# CC2530_PCB_Updated_Antenna_Stim_EMG-ROAC.net
KiCad netlist of a schematic drawn in EAGLE
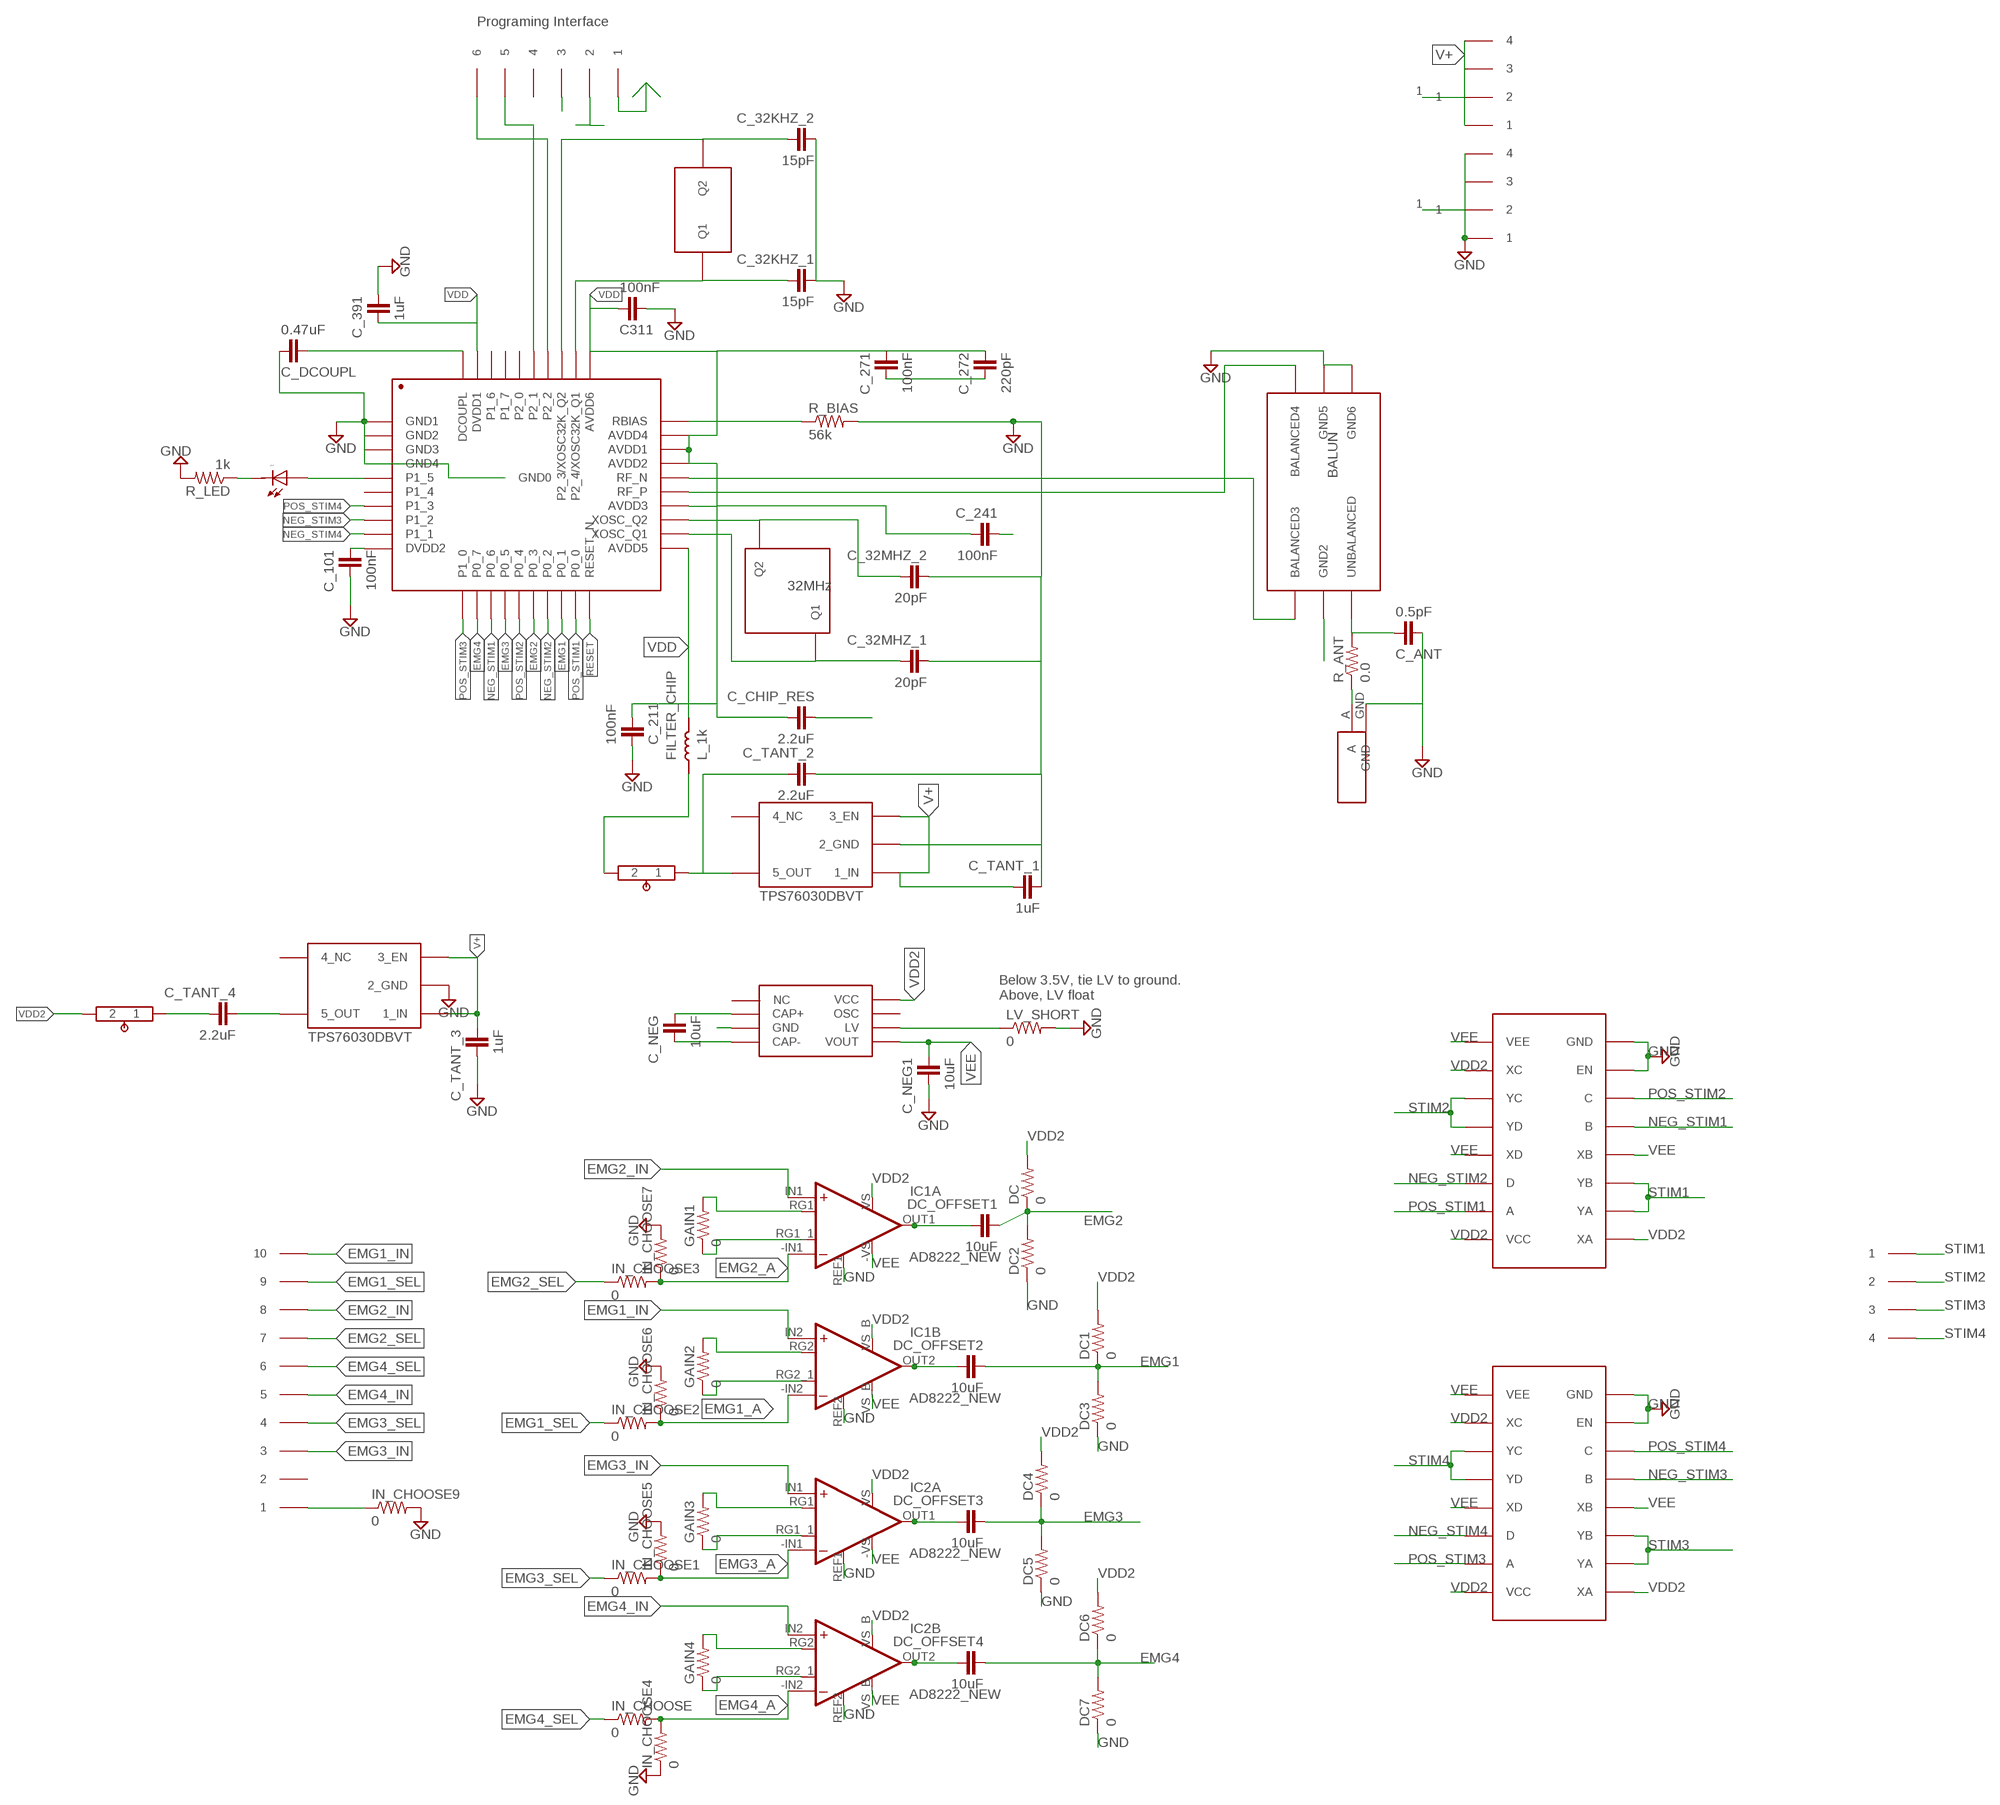
[diagram p0: schematic, sheet 1]

(export (version "E")
  (design (tool "Eeschema 10.0.6"))
  (components
    (comp (ref "32KHZ")
      (value "X32.768KHZ")
      (footprint "eagle-import:X32.768KHZ")
      (libsource (lib "eagle-import") (part "X32.768KHZ"))
    )
    (comp (ref "C311")
      (value "100nF")
      (footprint "eagle-import:0201_R_L_C")
      (libsource (lib "eagle-import") (part "0Y0X_C0201"))
    )
    (comp (ref "C_32KHZ_1")
      (value "15pF")
      (footprint "eagle-import:0201_R_L_C")
      (libsource (lib "eagle-import") (part "0Y0X_C0201"))
    )
    (comp (ref "C_32KHZ_2")
      (value "15pF")
      (footprint "eagle-import:0201_R_L_C")
      (libsource (lib "eagle-import") (part "0Y0X_C0201"))
    )
    (comp (ref "C_32MHZ_1")
      (value "20pF")
      (footprint "eagle-import:0201_R_L_C")
      (libsource (lib "eagle-import") (part "0Y0X_C0201"))
    )
    (comp (ref "C_32MHZ_2")
      (value "20pF")
      (footprint "eagle-import:0201_R_L_C")
      (libsource (lib "eagle-import") (part "0Y0X_C0201"))
    )
    (comp (ref "C_101")
      (value "100nF")
      (footprint "eagle-import:0201_R_L_C")
      (libsource (lib "eagle-import") (part "0Y0X_C0201"))
    )
    (comp (ref "C_211")
      (value "100nF")
      (footprint "eagle-import:0201_R_L_C")
      (libsource (lib "eagle-import") (part "0Y0X_C0201"))
    )
    (comp (ref "C_241")
      (value "100nF")
      (footprint "eagle-import:0201_R_L_C")
      (libsource (lib "eagle-import") (part "0Y0X_C0201"))
    )
    (comp (ref "C_271")
      (value "100nF")
      (footprint "eagle-import:0201_R_L_C")
      (libsource (lib "eagle-import") (part "0Y0X_C0201"))
    )
    (comp (ref "C_272")
      (value "220pF")
      (footprint "eagle-import:0201_R_L_C")
      (libsource (lib "eagle-import") (part "0Y0X_C0201"))
    )
    (comp (ref "C_391")
      (value "1uF")
      (footprint "eagle-import:0201_R_L_C")
      (libsource (lib "eagle-import") (part "0Y0X_C0201"))
    )
    (comp (ref "C_ANT")
      (value "0.5pF")
      (footprint "eagle-import:0201_R_L_C")
      (libsource (lib "eagle-import") (part "0Y0X_C0201"))
    )
    (comp (ref "C_CHIP_RES")
      (value "2.2uF")
      (footprint "eagle-import:0402_R_L_C")
      (libsource (lib "eagle-import") (part "0Y0X_C0402"))
    )
    (comp (ref "C_DCOUPL")
      (value "0.47uF")
      (footprint "eagle-import:0201_R_L_C")
      (libsource (lib "eagle-import") (part "0Y0X_C0201"))
    )
    (comp (ref "C_NEG")
      (value "10uF")
      (footprint "eagle-import:0402_R_L_C")
      (libsource (lib "eagle-import") (part "0Y0X_C0402"))
    )
    (comp (ref "C_NEG1")
      (value "10uF")
      (footprint "eagle-import:0402_R_L_C")
      (libsource (lib "eagle-import") (part "0Y0X_C0402"))
    )
    (comp (ref "C_TANT_1")
      (value "1uF")
      (footprint "eagle-import:0603_R_L_C")
      (libsource (lib "eagle-import") (part "0Y0X_C0603"))
    )
    (comp (ref "C_TANT_2")
      (value "2.2uF")
      (footprint "eagle-import:0603_R_L_C")
      (libsource (lib "eagle-import") (part "0Y0X_C0603"))
    )
    (comp (ref "C_TANT_3")
      (value "1uF")
      (footprint "eagle-import:0603_R_L_C")
      (libsource (lib "eagle-import") (part "0Y0X_C0603"))
    )
    (comp (ref "C_TANT_4")
      (value "2.2uF")
      (footprint "eagle-import:0603_R_L_C")
      (libsource (lib "eagle-import") (part "0Y0X_C0603"))
    )
    (comp (ref "DC")
      (value "0")
      (footprint "eagle-import:0402_R_L_C")
      (libsource (lib "eagle-import") (part "0Y0X_R0402"))
    )
    (comp (ref "DC1")
      (value "0")
      (footprint "eagle-import:0402_R_L_C")
      (libsource (lib "eagle-import") (part "0Y0X_R0402"))
    )
    (comp (ref "DC2")
      (value "0")
      (footprint "eagle-import:0402_R_L_C")
      (libsource (lib "eagle-import") (part "0Y0X_R0402"))
    )
    (comp (ref "DC3")
      (value "0")
      (footprint "eagle-import:0402_R_L_C")
      (libsource (lib "eagle-import") (part "0Y0X_R0402"))
    )
    (comp (ref "DC4")
      (value "0")
      (footprint "eagle-import:0402_R_L_C")
      (libsource (lib "eagle-import") (part "0Y0X_R0402"))
    )
    (comp (ref "DC5")
      (value "0")
      (footprint "eagle-import:0402_R_L_C")
      (libsource (lib "eagle-import") (part "0Y0X_R0402"))
    )
    (comp (ref "DC6")
      (value "0")
      (footprint "eagle-import:0402_R_L_C")
      (libsource (lib "eagle-import") (part "0Y0X_R0402"))
    )
    (comp (ref "DC7")
      (value "0")
      (footprint "eagle-import:0402_R_L_C")
      (libsource (lib "eagle-import") (part "0Y0X_R0402"))
    )
    (comp (ref "DC_OFFSET1")
      (value "10uF")
      (footprint "eagle-import:0402_R_L_C")
      (libsource (lib "eagle-import") (part "0Y0X_C0402"))
    )
    (comp (ref "DC_OFFSET2")
      (value "10uF")
      (footprint "eagle-import:0402_R_L_C")
      (libsource (lib "eagle-import") (part "0Y0X_C0402"))
    )
    (comp (ref "DC_OFFSET3")
      (value "10uF")
      (footprint "eagle-import:0402_R_L_C")
      (libsource (lib "eagle-import") (part "0Y0X_C0402"))
    )
    (comp (ref "DC_OFFSET4")
      (value "10uF")
      (footprint "eagle-import:0402_R_L_C")
      (libsource (lib "eagle-import") (part "0Y0X_C0402"))
    )
    (comp (ref "FILTER_CHIP")
      (value "L_1k")
      (footprint "eagle-import:0402_R_L_C")
      (libsource (lib "eagle-import") (part "0Y0X_L0402"))
    )
    (comp (ref "GAIN1")
      (value "0")
      (footprint "eagle-import:0402_R_L_C")
      (libsource (lib "eagle-import") (part "0Y0X_R0402"))
    )
    (comp (ref "GAIN2")
      (value "0")
      (footprint "eagle-import:0402_R_L_C")
      (libsource (lib "eagle-import") (part "0Y0X_R0402"))
    )
    (comp (ref "GAIN3")
      (value "0")
      (footprint "eagle-import:0402_R_L_C")
      (libsource (lib "eagle-import") (part "0Y0X_R0402"))
    )
    (comp (ref "GAIN4")
      (value "0")
      (footprint "eagle-import:0402_R_L_C")
      (libsource (lib "eagle-import") (part "0Y0X_R0402"))
    )
    (comp (ref "GND_IN")
      (value "FFC4POS")
      (footprint "eagle-import:FFC4POS")
      (libsource (lib "eagle-import") (part "FFC4POS"))
    )
    (comp (ref "IC1")
      (value "AD8222_NEW")
      (footprint "eagle-import:QFN-16")
      (libsource (lib "eagle-import") (part "AD8222_NEW"))
    )
    (comp (ref "IC2")
      (value "AD8222_NEW")
      (footprint "eagle-import:QFN-16")
      (libsource (lib "eagle-import") (part "AD8222_NEW"))
    )
    (comp (ref "INVERTED_F-ANTENNA")
      (value "ANTENNA")
      (footprint "eagle-import:ANTENNA")
      (libsource (lib "eagle-import") (part "ANTENNA"))
    )
    (comp (ref "IN_CHOOSE")
      (value "0")
      (footprint "eagle-import:0201_R_L_C")
      (libsource (lib "eagle-import") (part "0Y0X_R0201"))
    )
    (comp (ref "IN_CHOOSE1")
      (value "0")
      (footprint "eagle-import:0201_R_L_C")
      (libsource (lib "eagle-import") (part "0Y0X_R0201"))
    )
    (comp (ref "IN_CHOOSE2")
      (value "0")
      (footprint "eagle-import:0201_R_L_C")
      (libsource (lib "eagle-import") (part "0Y0X_R0201"))
    )
    (comp (ref "IN_CHOOSE3")
      (value "0")
      (footprint "eagle-import:0201_R_L_C")
      (libsource (lib "eagle-import") (part "0Y0X_R0201"))
    )
    (comp (ref "IN_CHOOSE4")
      (value "0")
      (footprint "eagle-import:0201_R_L_C")
      (libsource (lib "eagle-import") (part "0Y0X_R0201"))
    )
    (comp (ref "IN_CHOOSE5")
      (value "0")
      (footprint "eagle-import:0201_R_L_C")
      (libsource (lib "eagle-import") (part "0Y0X_R0201"))
    )
    (comp (ref "IN_CHOOSE6")
      (value "0")
      (footprint "eagle-import:0201_R_L_C")
      (libsource (lib "eagle-import") (part "0Y0X_R0201"))
    )
    (comp (ref "IN_CHOOSE7")
      (value "0")
      (footprint "eagle-import:0201_R_L_C")
      (libsource (lib "eagle-import") (part "0Y0X_R0201"))
    )
    (comp (ref "IN_CHOOSE9")
      (value "0")
      (footprint "eagle-import:0201_R_L_C")
      (libsource (lib "eagle-import") (part "0Y0X_R0201"))
    )
    (comp (ref "LED")
      (value "LED0603")
      (footprint "eagle-import:0603_R_L_C")
      (libsource (lib "eagle-import") (part "LED0603"))
    )
    (comp (ref "LV_SHORT")
      (value "0")
      (footprint "eagle-import:0402_R_L_C")
      (libsource (lib "eagle-import") (part "0Y0X_R0402"))
    )
    (comp (ref "R_ANT")
      (value "0.0")
      (footprint "eagle-import:0201_R_L_C")
      (libsource (lib "eagle-import") (part "0Y0X_R0201"))
    )
    (comp (ref "R_BIAS")
      (value "56k")
      (footprint "eagle-import:0201_R_L_C")
      (libsource (lib "eagle-import") (part "0Y0X_R0201"))
    )
    (comp (ref "R_LED")
      (value "1k")
      (footprint "eagle-import:0402_R_L_C")
      (libsource (lib "eagle-import") (part "0Y0X_R0402"))
    )
    (comp (ref "U$1")
      (value "CC2530")
      (footprint "eagle-import:CC2530")
      (libsource (lib "eagle-import") (part "CC2530"))
    )
    (comp (ref "U$2")
      (value "BALUN")
      (footprint "eagle-import:BALUN")
      (libsource (lib "eagle-import") (part "BALUN"))
    )
    (comp (ref "U$3")
      (value "X32MHZ")
      (footprint "eagle-import:X32MHZ")
      (fields (field (name "X") "32MHz"))
      (libsource (lib "eagle-import") (part "X32MHZ"))
    )
    (comp (ref "U$4")
      (value "TL7660")
      (footprint "eagle-import:S-PDSO-G8")
      (libsource (lib "eagle-import") (part "TL7660"))
    )
    (comp (ref "U$5")
      (value "MC74HC4316A")
      (footprint "eagle-import:SOIC-16-ON-SEMI")
      (libsource (lib "eagle-import") (part "MC74HC4316A"))
    )
    (comp (ref "U$6")
      (value "MC74HC4316A")
      (footprint "eagle-import:SOIC-16-ON-SEMI")
      (libsource (lib "eagle-import") (part "MC74HC4316A"))
    )
    (comp (ref "U$7")
      (value "FFC10POS")
      (footprint "eagle-import:FFC10POS")
      (libsource (lib "eagle-import") (part "FFC10POS"))
    )
    (comp (ref "U$8")
      (value "REGULATOR")
      (footprint "eagle-import:REGULATOR")
      (libsource (lib "eagle-import") (part "REGULATOR"))
    )
    (comp (ref "U$9")
      (value "SWITCH_MANUAL")
      (footprint "eagle-import:SWITCH_MANUAL")
      (libsource (lib "eagle-import") (part "SWITCH_MANUAL"))
    )
    (comp (ref "U$10")
      (value "REGULATOR")
      (footprint "eagle-import:REGULATOR")
      (libsource (lib "eagle-import") (part "REGULATOR"))
    )
    (comp (ref "U$17")
      (value "FFC6POS")
      (footprint "eagle-import:FFC6POS")
      (libsource (lib "eagle-import") (part "FFC6POS"))
    )
    (comp (ref "U$18")
      (value "SWITCH_MANUAL")
      (footprint "eagle-import:SWITCH_MANUAL")
      (libsource (lib "eagle-import") (part "SWITCH_MANUAL"))
    )
    (comp (ref "U$28")
      (value "FFC4POS")
      (footprint "eagle-import:FFC4POS")
      (libsource (lib "eagle-import") (part "FFC4POS"))
    )
    (comp (ref "V+_IN")
      (value "FFC4POS")
      (footprint "eagle-import:FFC4POS")
      (libsource (lib "eagle-import") (part "FFC4POS"))
    )
    (comp (ref "WIRE+")
      (value "DRILL_CONNECT")
      (footprint "eagle-import:DRILL_CONNECT")
      (libsource (lib "eagle-import") (part "DRILL_CONNECT"))
    )
    (comp (ref "WIRE-")
      (value "DRILL_CONNECT")
      (footprint "eagle-import:DRILL_CONNECT")
      (libsource (lib "eagle-import") (part "DRILL_CONNECT"))
    )
  )
  (nets
    (net (code "1") (name "/NC") (class "Default")
      (node (ref "U$4") (pin "1") (pinfunction "NC_1") (pintype "power_in"))
    )
    (net (code "2") (name "/OSC") (class "Default")
      (node (ref "U$4") (pin "7") (pinfunction "OSC_7") (pintype "power_in"))
    )
    (net (code "3") (name "/STIM1") (class "Default")
      (node (ref "U$28") (pin "1") (pinfunction "1_1") (pintype "bidirectional"))
      (node (ref "U$5") (pin "2") (pinfunction "YA_2") (pintype "output"))
      (node (ref "U$5") (pin "3") (pinfunction "YB_3") (pintype "output"))
    )
    (net (code "4") (name "/STIM2") (class "Default")
      (node (ref "U$28") (pin "2") (pinfunction "2_2") (pintype "bidirectional"))
      (node (ref "U$5") (pin "11") (pinfunction "YC_11") (pintype "output"))
      (node (ref "U$5") (pin "12") (pinfunction "YD_12") (pintype "output"))
    )
    (net (code "5") (name "/STIM3") (class "Default")
      (node (ref "U$28") (pin "3") (pinfunction "3_3") (pintype "bidirectional"))
      (node (ref "U$6") (pin "2") (pinfunction "YA_2") (pintype "output"))
      (node (ref "U$6") (pin "3") (pinfunction "YB_3") (pintype "output"))
    )
    (net (code "6") (name "/STIM4") (class "Default")
      (node (ref "U$28") (pin "4") (pinfunction "4_4") (pintype "bidirectional"))
      (node (ref "U$6") (pin "11") (pinfunction "YC_11") (pintype "output"))
      (node (ref "U$6") (pin "12") (pinfunction "YD_12") (pintype "output"))
    )
    (net (code "7") (name "EMG1") (class "Default")
      (node (ref "DC1") (pin "1") (pinfunction "1_1") (pintype "passive"))
      (node (ref "DC3") (pin "2") (pinfunction "2_2") (pintype "passive"))
      (node (ref "DC_OFFSET2") (pin "2") (pinfunction "2_2") (pintype "passive"))
      (node (ref "U$1") (pin "P0_1") (pinfunction "P0_1_P0_1") (pintype "bidirectional"))
    )
    (net (code "8") (name "EMG1_A") (class "Default")
      (node (ref "IC1") (pin "-IN2") (pinfunction "-IN_-IN2") (pintype "input"))
      (node (ref "IN_CHOOSE2") (pin "2") (pinfunction "2_2") (pintype "passive"))
      (node (ref "IN_CHOOSE6") (pin "1") (pinfunction "1_1") (pintype "passive"))
    )
    (net (code "9") (name "EMG1_IN") (class "Default")
      (node (ref "IC1") (pin "IN2") (pinfunction "+IN_IN2") (pintype "input"))
      (node (ref "U$7") (pin "10") (pinfunction "10_10") (pintype "bidirectional"))
    )
    (net (code "10") (name "EMG1_SEL") (class "Default")
      (node (ref "IN_CHOOSE2") (pin "1") (pinfunction "1_1") (pintype "passive"))
      (node (ref "U$7") (pin "9") (pinfunction "9_9") (pintype "bidirectional"))
    )
    (net (code "11") (name "EMG2") (class "Default")
      (node (ref "DC") (pin "1") (pinfunction "1_1") (pintype "passive"))
      (node (ref "DC2") (pin "2") (pinfunction "2_2") (pintype "passive"))
      (node (ref "DC_OFFSET1") (pin "2") (pinfunction "2_2") (pintype "passive"))
      (node (ref "U$1") (pin "P0_3") (pinfunction "P0_3_P0_3") (pintype "bidirectional"))
    )
    (net (code "12") (name "EMG2_A") (class "Default")
      (node (ref "IC1") (pin "-IN1") (pinfunction "-IN_-IN1") (pintype "input"))
      (node (ref "IN_CHOOSE3") (pin "2") (pinfunction "2_2") (pintype "passive"))
      (node (ref "IN_CHOOSE7") (pin "1") (pinfunction "1_1") (pintype "passive"))
    )
    (net (code "13") (name "EMG2_IN") (class "Default")
      (node (ref "IC1") (pin "IN1") (pinfunction "+IN_IN1") (pintype "input"))
      (node (ref "U$7") (pin "8") (pinfunction "8_8") (pintype "bidirectional"))
    )
    (net (code "14") (name "EMG2_SEL") (class "Default")
      (node (ref "IN_CHOOSE3") (pin "1") (pinfunction "1_1") (pintype "passive"))
      (node (ref "U$7") (pin "7") (pinfunction "7_7") (pintype "bidirectional"))
    )
    (net (code "15") (name "EMG3") (class "Default")
      (node (ref "DC4") (pin "1") (pinfunction "1_1") (pintype "passive"))
      (node (ref "DC5") (pin "2") (pinfunction "2_2") (pintype "passive"))
      (node (ref "DC_OFFSET3") (pin "2") (pinfunction "2_2") (pintype "passive"))
      (node (ref "U$1") (pin "P0_5") (pinfunction "P0_5_P0_5") (pintype "bidirectional"))
    )
    (net (code "16") (name "EMG3_A") (class "Default")
      (node (ref "IC2") (pin "-IN1") (pinfunction "-IN_-IN1") (pintype "input"))
      (node (ref "IN_CHOOSE1") (pin "2") (pinfunction "2_2") (pintype "passive"))
      (node (ref "IN_CHOOSE5") (pin "1") (pinfunction "1_1") (pintype "passive"))
    )
    (net (code "17") (name "EMG3_IN") (class "Default")
      (node (ref "IC2") (pin "IN1") (pinfunction "+IN_IN1") (pintype "input"))
      (node (ref "U$7") (pin "3") (pinfunction "3_3") (pintype "bidirectional"))
    )
    (net (code "18") (name "EMG3_SEL") (class "Default")
      (node (ref "IN_CHOOSE1") (pin "1") (pinfunction "1_1") (pintype "passive"))
      (node (ref "U$7") (pin "4") (pinfunction "4_4") (pintype "bidirectional"))
    )
    (net (code "19") (name "EMG4") (class "Default")
      (node (ref "DC6") (pin "1") (pinfunction "1_1") (pintype "passive"))
      (node (ref "DC7") (pin "2") (pinfunction "2_2") (pintype "passive"))
      (node (ref "DC_OFFSET4") (pin "2") (pinfunction "2_2") (pintype "passive"))
      (node (ref "U$1") (pin "P0_7") (pinfunction "P0_7_P0_7") (pintype "bidirectional"))
    )
    (net (code "20") (name "EMG4_A") (class "Default")
      (node (ref "IC2") (pin "-IN2") (pinfunction "-IN_-IN2") (pintype "input"))
      (node (ref "IN_CHOOSE") (pin "2") (pinfunction "2_2") (pintype "passive"))
      (node (ref "IN_CHOOSE4") (pin "2") (pinfunction "2_2") (pintype "passive"))
    )
    (net (code "21") (name "EMG4_IN") (class "Default")
      (node (ref "IC2") (pin "IN2") (pinfunction "+IN_IN2") (pintype "input"))
      (node (ref "U$7") (pin "5") (pinfunction "5_5") (pintype "bidirectional"))
    )
    (net (code "22") (name "EMG4_SEL") (class "Default")
      (node (ref "IN_CHOOSE") (pin "1") (pinfunction "1_1") (pintype "passive"))
      (node (ref "U$7") (pin "6") (pinfunction "6_6") (pintype "bidirectional"))
    )
    (net (code "23") (name "GND") (class "Default")
      (node (ref "C311") (pin "1") (pinfunction "1_1") (pintype "passive"))
      (node (ref "C_101") (pin "1") (pinfunction "1_1") (pintype "passive"))
      (node (ref "C_211") (pin "2") (pinfunction "2_2") (pintype "passive"))
      (node (ref "C_241") (pin "2") (pinfunction "2_2") (pintype "passive"))
      (node (ref "C_271") (pin "1") (pinfunction "1_1") (pintype "passive"))
      (node (ref "C_272") (pin "1") (pinfunction "1_1") (pintype "passive"))
      (node (ref "C_32KHZ_1") (pin "2") (pinfunction "2_2") (pintype "passive"))
      (node (ref "C_32KHZ_2") (pin "2") (pinfunction "2_2") (pintype "passive"))
      (node (ref "C_32MHZ_1") (pin "2") (pinfunction "2_2") (pintype "passive"))
      (node (ref "C_32MHZ_2") (pin "2") (pinfunction "2_2") (pintype "passive"))
      (node (ref "C_391") (pin "2") (pinfunction "2_2") (pintype "passive"))
      (node (ref "C_ANT") (pin "1") (pinfunction "1_1") (pintype "passive"))
      (node (ref "C_CHIP_RES") (pin "2") (pinfunction "2_2") (pintype "passive"))
      (node (ref "C_DCOUPL") (pin "2") (pinfunction "2_2") (pintype "passive"))
      (node (ref "C_NEG1") (pin "1") (pinfunction "1_1") (pintype "passive"))
      (node (ref "C_TANT_1") (pin "2") (pinfunction "2_2") (pintype "passive"))
      (node (ref "C_TANT_2") (pin "2") (pinfunction "2_2") (pintype "passive"))
      (node (ref "C_TANT_3") (pin "1") (pinfunction "1_1") (pintype "passive"))
      (node (ref "DC2") (pin "1") (pinfunction "1_1") (pintype "passive"))
      (node (ref "DC3") (pin "1") (pinfunction "1_1") (pintype "passive"))
      (node (ref "DC5") (pin "1") (pinfunction "1_1") (pintype "passive"))
      (node (ref "DC7") (pin "1") (pinfunction "1_1") (pintype "passive"))
      (node (ref "GND_IN") (pin "1") (pinfunction "1_1") (pintype "bidirectional"))
      (node (ref "GND_IN") (pin "2") (pinfunction "2_2") (pintype "bidirectional"))
      (node (ref "GND_IN") (pin "3") (pinfunction "3_3") (pintype "bidirectional"))
      (node (ref "GND_IN") (pin "4") (pinfunction "4_4") (pintype "bidirectional"))
      (node (ref "IC1") (pin "REF1") (pinfunction "REF_REF1") (pintype "input"))
      (node (ref "IC1") (pin "REF2") (pinfunction "REF_REF2") (pintype "input"))
      (node (ref "IC2") (pin "REF1") (pinfunction "REF_REF1") (pintype "input"))
      (node (ref "IC2") (pin "REF2") (pinfunction "REF_REF2") (pintype "input"))
      (node (ref "INVERTED_F-ANTENNA") (pin "GND") (pinfunction "GND_GND") (pintype "power_in"))
      (node (ref "IN_CHOOSE4") (pin "1") (pinfunction "1_1") (pintype "passive"))
      (node (ref "IN_CHOOSE5") (pin "2") (pinfunction "2_2") (pintype "passive"))
      (node (ref "IN_CHOOSE6") (pin "2") (pinfunction "2_2") (pintype "passive"))
      (node (ref "IN_CHOOSE7") (pin "2") (pinfunction "2_2") (pintype "passive"))
      (node (ref "IN_CHOOSE9") (pin "2") (pinfunction "2_2") (pintype "passive"))
      (node (ref "LV_SHORT") (pin "2") (pinfunction "2_2") (pintype "passive"))
      (node (ref "R_BIAS") (pin "2") (pinfunction "2_2") (pintype "passive"))
      (node (ref "R_LED") (pin "2") (pinfunction "2_2") (pintype "passive"))
      (node (ref "U$1") (pin "GND0") (pinfunction "GND0_GND0") (pintype "power_in"))
      (node (ref "U$1") (pin "GND001") (pinfunction "GND0_GND001") (pintype "power_in"))
      (node (ref "U$1") (pin "GND002") (pinfunction "GND0_GND002") (pintype "power_in"))
      (node (ref "U$1") (pin "GND003") (pinfunction "GND0_GND003") (pintype "power_in"))
      (node (ref "U$1") (pin "GND004") (pinfunction "GND0_GND004") (pintype "power_in"))
      (node (ref "U$1") (pin "GND005") (pinfunction "GND0_GND005") (pintype "power_in"))
      (node (ref "U$1") (pin "GND006") (pinfunction "GND0_GND006") (pintype "power_in"))
      (node (ref "U$1") (pin "GND007") (pinfunction "GND0_GND007") (pintype "power_in"))
      (node (ref "U$1") (pin "GND008") (pinfunction "GND0_GND008") (pintype "power_in"))
      (node (ref "U$1") (pin "GND009") (pinfunction "GND0_GND009") (pintype "power_in"))
      (node (ref "U$1") (pin "GND010") (pinfunction "GND0_GND010") (pintype "power_in"))
      (node (ref "U$1") (pin "GND011") (pinfunction "GND0_GND011") (pintype "power_in"))
      (node (ref "U$1") (pin "GND012") (pinfunction "GND0_GND012") (pintype "power_in"))
      (node (ref "U$1") (pin "GND013") (pinfunction "GND0_GND013") (pintype "power_in"))
      (node (ref "U$1") (pin "GND014") (pinfunction "GND0_GND014") (pintype "power_in"))
      (node (ref "U$1") (pin "GND015") (pinfunction "GND0_GND015") (pintype "power_in"))
      (node (ref "U$1") (pin "GND016") (pinfunction "GND0_GND016") (pintype "power_in"))
      (node (ref "U$1") (pin "GND1") (pinfunction "GND1_GND1") (pintype "power_in"))
      (node (ref "U$1") (pin "GND2") (pinfunction "GND2_GND2") (pintype "power_in"))
      (node (ref "U$1") (pin "GND3") (pinfunction "GND3_GND3") (pintype "power_in"))
      (node (ref "U$1") (pin "GND4") (pinfunction "GND4_GND4") (pintype "power_in"))
      (node (ref "U$10") (pin "2") (pinfunction "2_GND_2") (pintype "power_in"))
      (node (ref "U$17") (pin "2") (pinfunction "2_2") (pintype "bidirectional"))
      (node (ref "U$2") (pin "GND2") (pinfunction "GND2_GND2") (pintype "power_in"))
      (node (ref "U$2") (pin "GND5") (pinfunction "GND5_GND5") (pintype "power_in"))
      (node (ref "U$2") (pin "GND6") (pinfunction "GND6_GND6") (pintype "power_in"))
      (node (ref "U$4") (pin "3") (pinfunction "GND_3") (pintype "power_in"))
      (node (ref "U$5") (pin "7") (pinfunction "EN_7") (pintype "input"))
      (node (ref "U$5") (pin "8") (pinfunction "GND_8") (pintype "power_in"))
      (node (ref "U$6") (pin "7") (pinfunction "EN_7") (pintype "input"))
      (node (ref "U$6") (pin "8") (pinfunction "GND_8") (pintype "power_in"))
      (node (ref "U$8") (pin "2") (pinfunction "2_GND_2") (pintype "power_in"))
      (node (ref "WIRE-") (pin "1") (pinfunction "1_1") (pintype "bidirectional"))
    )
    (net (code "24") (name "NEG_STIM1") (class "Default")
      (node (ref "U$1") (pin "P0_6") (pinfunction "P0_6_P0_6") (pintype "bidirectional"))
      (node (ref "U$5") (pin "5") (pinfunction "B_5") (pintype "input"))
    )
    (net (code "25") (name "NEG_STIM2") (class "Default")
      (node (ref "U$1") (pin "P0_2") (pinfunction "P0_2_P0_2") (pintype "bidirectional"))
      (node (ref "U$5") (pin "14") (pinfunction "D_14") (pintype "input"))
    )
    (net (code "26") (name "NEG_STIM3") (class "Default")
      (node (ref "U$1") (pin "P1_2") (pinfunction "P1_2_P1_2") (pintype "bidirectional"))
      (node (ref "U$6") (pin "5") (pinfunction "B_5") (pintype "input"))
    )
    (net (code "27") (name "NEG_STIM4") (class "Default")
      (node (ref "U$1") (pin "P1_1") (pinfunction "P1_1_P1_1") (pintype "bidirectional"))
      (node (ref "U$6") (pin "14") (pinfunction "D_14") (pintype "input"))
    )
    (net (code "28") (name "Net-(32KHZ-PadQ1)") (class "Default")
      (node (ref "32KHZ") (pin "Q1") (pinfunction "Q1_Q1") (pintype "bidirectional"))
      (node (ref "C_32KHZ_1") (pin "1") (pinfunction "1_1") (pintype "passive"))
      (node (ref "U$1") (pin "P2_4/XOSC32K_Q1") (pinfunction "P2_4/XOSC32K_Q1_P2_4/XOSC32K_Q1") (pintype "bidirectional"))
    )
    (net (code "29") (name "Net-(32KHZ-PadQ2)") (class "Default")
      (node (ref "32KHZ") (pin "Q2") (pinfunction "Q2_Q2") (pintype "bidirectional"))
      (node (ref "C_32KHZ_2") (pin "1") (pinfunction "1_1") (pintype "passive"))
      (node (ref "U$1") (pin "P2_3/XOSC32K_Q2") (pinfunction "P2_3/XOSC32K_Q2_P2_3/XOSC32K_Q2") (pintype "bidirectional"))
    )
    (net (code "30") (name "Net-(C_32MHZ_1-Pad1)") (class "Default")
      (node (ref "C_32MHZ_1") (pin "1") (pinfunction "1_1") (pintype "passive"))
      (node (ref "U$1") (pin "XOSC_Q1") (pinfunction "XOSC_Q1_XOSC_Q1") (pintype "bidirectional"))
      (node (ref "U$3") (pin "Q1") (pinfunction "Q1_Q1") (pintype "bidirectional"))
    )
    (net (code "31") (name "Net-(C_32MHZ_2-Pad1)") (class "Default")
      (node (ref "C_32MHZ_2") (pin "1") (pinfunction "1_1") (pintype "passive"))
      (node (ref "U$1") (pin "XOSC_Q2") (pinfunction "XOSC_Q2_XOSC_Q2") (pintype "bidirectional"))
      (node (ref "U$3") (pin "Q2") (pinfunction "Q2_Q2") (pintype "bidirectional"))
    )
    (net (code "32") (name "Net-(C_ANT-Pad2)") (class "Default")
      (node (ref "C_ANT") (pin "2") (pinfunction "2_2") (pintype "passive"))
      (node (ref "R_ANT") (pin "2") (pinfunction "2_2") (pintype "passive"))
      (node (ref "U$2") (pin "UNBALANCED") (pinfunction "UNBALANCED_UNBALANCED") (pintype "bidirectional"))
    )
    (net (code "33") (name "Net-(C_DCOUPL-Pad1)") (class "Default")
      (node (ref "C_DCOUPL") (pin "1") (pinfunction "1_1") (pintype "passive"))
      (node (ref "U$1") (pin "DCOUPL") (pinfunction "DCOUPL_DCOUPL") (pintype "power_in"))
    )
    (net (code "34") (name "Net-(C_TANT_4-Pad1)") (class "Default")
      (node (ref "C_TANT_4") (pin "1") (pinfunction "1_1") (pintype "passive"))
      (node (ref "U$9") (pin "1") (pinfunction "1_1") (pintype "bidirectional"))
    )
    (net (code "35") (name "Net-(FILTER_CHIP-Pad1)") (class "Default")
      (node (ref "FILTER_CHIP") (pin "1") (pinfunction "1_1") (pintype "bidirectional"))
      (node (ref "U$18") (pin "2") (pinfunction "2_2") (pintype "bidirectional"))
    )
    (net (code "36") (name "Net-(GAIN1-Pad1)") (class "Default")
      (node (ref "GAIN1") (pin "1") (pinfunction "1_1") (pintype "passive"))
      (node (ref "IC1") (pin "RG1_1") (pinfunction "RG1_1_RG1_1") (pintype "input"))
    )
    (net (code "37") (name "Net-(GAIN1-Pad2)") (class "Default")
      (node (ref "GAIN1") (pin "2") (pinfunction "2_2") (pintype "passive"))
      (node (ref "IC1") (pin "RG1") (pinfunction "RG1_RG1") (pintype "input"))
    )
    (net (code "38") (name "Net-(GAIN3-Pad1)") (class "Default")
      (node (ref "GAIN3") (pin "1") (pinfunction "1_1") (pintype "passive"))
      (node (ref "IC2") (pin "RG1_1") (pinfunction "RG1_1_RG1_1") (pintype "input"))
    )
    (net (code "39") (name "Net-(GAIN3-Pad2)") (class "Default")
      (node (ref "GAIN3") (pin "2") (pinfunction "2_2") (pintype "passive"))
      (node (ref "IC2") (pin "RG1") (pinfunction "RG1_RG1") (pintype "input"))
    )
    (net (code "40") (name "Net-(IC1A-OUT)") (class "Default")
      (node (ref "DC_OFFSET1") (pin "1") (pinfunction "1_1") (pintype "passive"))
      (node (ref "IC1") (pin "OUT1") (pinfunction "OUT_OUT1") (pintype "input"))
    )
    (net (code "41") (name "Net-(IC1B-OUT)") (class "Default")
      (node (ref "DC_OFFSET2") (pin "1") (pinfunction "1_1") (pintype "passive"))
      (node (ref "IC1") (pin "OUT2") (pinfunction "OUT_OUT2") (pintype "input"))
    )
    (net (code "42") (name "Net-(IC1B-RG1)") (class "Default")
      (node (ref "GAIN2") (pin "2") (pinfunction "2_2") (pintype "passive"))
      (node (ref "IC1") (pin "RG2") (pinfunction "RG1_RG2") (pintype "input"))
    )
    (net (code "43") (name "Net-(IC1B-RG1_1)") (class "Default")
      (node (ref "GAIN2") (pin "1") (pinfunction "1_1") (pintype "passive"))
      (node (ref "IC1") (pin "RG2_1") (pinfunction "RG1_1_RG2_1") (pintype "input"))
    )
    (net (code "44") (name "Net-(IC2A-OUT)") (class "Default")
      (node (ref "DC_OFFSET3") (pin "1") (pinfunction "1_1") (pintype "passive"))
      (node (ref "IC2") (pin "OUT1") (pinfunction "OUT_OUT1") (pintype "input"))
    )
    (net (code "45") (name "Net-(IC2B-OUT)") (class "Default")
      (node (ref "DC_OFFSET4") (pin "1") (pinfunction "1_1") (pintype "passive"))
      (node (ref "IC2") (pin "OUT2") (pinfunction "OUT_OUT2") (pintype "input"))
    )
    (net (code "46") (name "Net-(IC2B-RG1)") (class "Default")
      (node (ref "GAIN4") (pin "2") (pinfunction "2_2") (pintype "passive"))
      (node (ref "IC2") (pin "RG2") (pinfunction "RG1_RG2") (pintype "input"))
    )
    (net (code "47") (name "Net-(IC2B-RG1_1)") (class "Default")
      (node (ref "GAIN4") (pin "1") (pinfunction "1_1") (pintype "passive"))
      (node (ref "IC2") (pin "RG2_1") (pinfunction "RG1_1_RG2_1") (pintype "input"))
    )
    (net (code "48") (name "Net-(INVERTED_F-ANTENNA-PadA)") (class "Default")
      (node (ref "INVERTED_F-ANTENNA") (pin "A") (pinfunction "A_A") (pintype "bidirectional"))
      (node (ref "R_ANT") (pin "1") (pinfunction "1_1") (pintype "passive"))
    )
    (net (code "49") (name "Net-(IN_CHOOSE9-Pad1)") (class "Default")
      (node (ref "IN_CHOOSE9") (pin "1") (pinfunction "1_1") (pintype "passive"))
      (node (ref "U$7") (pin "1") (pinfunction "1_1") (pintype "bidirectional"))
    )
    (net (code "50") (name "Net-(LED-A)") (class "Default")
      (node (ref "LED") (pin "1") (pinfunction "A_1") (pintype "passive"))
      (node (ref "U$1") (pin "P1_5") (pinfunction "P1_5_P1_5") (pintype "bidirectional"))
    )
    (net (code "51") (name "Net-(LED-C)") (class "Default")
      (node (ref "LED") (pin "2") (pinfunction "C_2") (pintype "passive"))
      (node (ref "R_LED") (pin "1") (pinfunction "1_1") (pintype "passive"))
    )
    (net (code "52") (name "Net-(R_BIAS-Pad1)") (class "Default")
      (node (ref "R_BIAS") (pin "1") (pinfunction "1_1") (pintype "passive"))
      (node (ref "U$1") (pin "RBIAS") (pinfunction "RBIAS_RBIAS") (pintype "bidirectional"))
    )
    (net (code "53") (name "Net-(U$1-PadP2_1)") (class "Default")
      (node (ref "U$1") (pin "P2_1") (pinfunction "P2_1_P2_1") (pintype "bidirectional"))
      (node (ref "U$17") (pin "5") (pinfunction "5_5") (pintype "bidirectional"))
    )
    (net (code "54") (name "Net-(U$1-PadP2_2)") (class "Default")
      (node (ref "U$1") (pin "P2_2") (pinfunction "P2_2_P2_2") (pintype "bidirectional"))
      (node (ref "U$17") (pin "6") (pinfunction "6_6") (pintype "bidirectional"))
    )
    (net (code "55") (name "Net-(U$1-PadRF_N)") (class "Default")
      (node (ref "U$1") (pin "RF_N") (pinfunction "RF_N_RF_N") (pintype "bidirectional"))
      (node (ref "U$2") (pin "BALANCED3") (pinfunction "BALANCED3_BALANCED3") (pintype "bidirectional"))
    )
    (net (code "56") (name "Net-(U$1-PadRF_P)") (class "Default")
      (node (ref "U$1") (pin "RF_P") (pinfunction "RF_P_RF_P") (pintype "bidirectional"))
      (node (ref "U$2") (pin "BALANCED4") (pinfunction "BALANCED4_BALANCED4") (pintype "bidirectional"))
    )
    (net (code "57") (name "Net-(U$4-CAP+)") (class "Default")
      (node (ref "C_NEG") (pin "2") (pinfunction "2_2") (pintype "passive"))
      (node (ref "U$4") (pin "2") (pinfunction "CAP+_2") (pintype "power_in"))
    )
    (net (code "58") (name "Net-(U$4-CAP-)") (class "Default")
      (node (ref "C_NEG") (pin "1") (pinfunction "1_1") (pintype "passive"))
      (node (ref "U$4") (pin "4") (pinfunction "CAP-_4") (pintype "power_in"))
    )
    (net (code "59") (name "Net-(U$4-LV)") (class "Default")
      (node (ref "LV_SHORT") (pin "1") (pinfunction "1_1") (pintype "passive"))
      (node (ref "U$4") (pin "6") (pinfunction "LV_6") (pintype "power_in"))
    )
    (net (code "60") (name "Net-(U$8-5_OUT)") (class "Default")
      (node (ref "C_TANT_4") (pin "2") (pinfunction "2_2") (pintype "passive"))
      (node (ref "U$8") (pin "5") (pinfunction "5_OUT_5") (pintype "bidirectional"))
    )
    (net (code "61") (name "Net-(U$10-5_OUT)") (class "Default")
      (node (ref "C_TANT_2") (pin "1") (pinfunction "1_1") (pintype "passive"))
      (node (ref "U$10") (pin "5") (pinfunction "5_OUT_5") (pintype "bidirectional"))
      (node (ref "U$18") (pin "1") (pinfunction "1_1") (pintype "bidirectional"))
    )
    (net (code "62") (name "POS_STIM1") (class "Default")
      (node (ref "U$1") (pin "P0_0") (pinfunction "P0_0_P0_0") (pintype "bidirectional"))
      (node (ref "U$5") (pin "15") (pinfunction "A_15") (pintype "input"))
    )
    (net (code "63") (name "POS_STIM2") (class "Default")
      (node (ref "U$1") (pin "P0_4") (pinfunction "P0_4_P0_4") (pintype "bidirectional"))
      (node (ref "U$5") (pin "6") (pinfunction "C_6") (pintype "input"))
    )
    (net (code "64") (name "POS_STIM3") (class "Default")
      (node (ref "U$1") (pin "P1_0") (pinfunction "P1_0_P1_0") (pintype "bidirectional"))
      (node (ref "U$6") (pin "15") (pinfunction "A_15") (pintype "input"))
    )
    (net (code "65") (name "POS_STIM4") (class "Default")
      (node (ref "U$1") (pin "P1_3") (pinfunction "P1_3_P1_3") (pintype "bidirectional"))
      (node (ref "U$6") (pin "6") (pinfunction "C_6") (pintype "input"))
    )
    (net (code "66") (name "RESET") (class "Default")
      (node (ref "U$1") (pin "RESET_N") (pinfunction "RESET_N_RESET_N") (pintype "input"))
      (node (ref "U$17") (pin "3") (pinfunction "3_3") (pintype "bidirectional"))
    )
    (net (code "67") (name "V+") (class "Default")
      (node (ref "C_TANT_1") (pin "1") (pinfunction "1_1") (pintype "passive"))
      (node (ref "C_TANT_3") (pin "2") (pinfunction "2_2") (pintype "passive"))
      (node (ref "U$10") (pin "1") (pinfunction "1_IN_1") (pintype "bidirectional"))
      (node (ref "U$10") (pin "3") (pinfunction "3_EN_3") (pintype "bidirectional"))
      (node (ref "U$8") (pin "1") (pinfunction "1_IN_1") (pintype "bidirectional"))
      (node (ref "U$8") (pin "3") (pinfunction "3_EN_3") (pintype "bidirectional"))
      (node (ref "V+_IN") (pin "1") (pinfunction "1_1") (pintype "bidirectional"))
      (node (ref "V+_IN") (pin "2") (pinfunction "2_2") (pintype "bidirectional"))
      (node (ref "V+_IN") (pin "3") (pinfunction "3_3") (pintype "bidirectional"))
      (node (ref "V+_IN") (pin "4") (pinfunction "4_4") (pintype "bidirectional"))
      (node (ref "WIRE+") (pin "1") (pinfunction "1_1") (pintype "bidirectional"))
    )
    (net (code "68") (name "VDD") (class "Default")
      (node (ref "C311") (pin "2") (pinfunction "2_2") (pintype "passive"))
      (node (ref "C_101") (pin "2") (pinfunction "2_2") (pintype "passive"))
      (node (ref "C_211") (pin "1") (pinfunction "1_1") (pintype "passive"))
      (node (ref "C_241") (pin "1") (pinfunction "1_1") (pintype "passive"))
      (node (ref "C_271") (pin "2") (pinfunction "2_2") (pintype "passive"))
      (node (ref "C_272") (pin "2") (pinfunction "2_2") (pintype "passive"))
      (node (ref "C_391") (pin "1") (pinfunction "1_1") (pintype "passive"))
      (node (ref "C_CHIP_RES") (pin "1") (pinfunction "1_1") (pintype "passive"))
      (node (ref "FILTER_CHIP") (pin "2") (pinfunction "2_2") (pintype "bidirectional"))
      (node (ref "U$1") (pin "AVDD1") (pinfunction "AVDD1_AVDD1") (pintype "power_in"))
      (node (ref "U$1") (pin "AVDD2") (pinfunction "AVDD2_AVDD2") (pintype "power_in"))
      (node (ref "U$1") (pin "AVDD3") (pinfunction "AVDD3_AVDD3") (pintype "power_in"))
      (node (ref "U$1") (pin "AVDD4") (pinfunction "AVDD4_AVDD4") (pintype "power_in"))
      (node (ref "U$1") (pin "AVDD5") (pinfunction "AVDD5_AVDD5") (pintype "power_in"))
      (node (ref "U$1") (pin "AVDD6") (pinfunction "AVDD6_AVDD6") (pintype "power_in"))
      (node (ref "U$1") (pin "DVDD1") (pinfunction "DVDD1_DVDD1") (pintype "power_in"))
      (node (ref "U$1") (pin "DVDD2") (pinfunction "DVDD2_DVDD2") (pintype "power_in"))
      (node (ref "U$17") (pin "1") (pinfunction "1_1") (pintype "bidirectional"))
    )
    (net (code "69") (name "VDD2") (class "Default")
      (node (ref "DC") (pin "2") (pinfunction "2_2") (pintype "passive"))
      (node (ref "DC1") (pin "2") (pinfunction "2_2") (pintype "passive"))
      (node (ref "DC4") (pin "2") (pinfunction "2_2") (pintype "passive"))
      (node (ref "DC6") (pin "2") (pinfunction "2_2") (pintype "passive"))
      (node (ref "IC1") (pin "VS") (pinfunction "V+_VS") (pintype "power_in"))
      (node (ref "IC1") (pin "VS_B") (pinfunction "V+_VS_B") (pintype "power_in"))
      (node (ref "IC2") (pin "VS") (pinfunction "V+_VS") (pintype "power_in"))
      (node (ref "IC2") (pin "VS_B") (pinfunction "V+_VS_B") (pintype "power_in"))
      (node (ref "U$4") (pin "8") (pinfunction "VCC_8") (pintype "power_in"))
      (node (ref "U$5") (pin "1") (pinfunction "XA_1") (pintype "input"))
      (node (ref "U$5") (pin "10") (pinfunction "XC_10") (pintype "input"))
      (node (ref "U$5") (pin "16") (pinfunction "VCC_16") (pintype "power_in"))
      (node (ref "U$6") (pin "1") (pinfunction "XA_1") (pintype "input"))
      (node (ref "U$6") (pin "10") (pinfunction "XC_10") (pintype "input"))
      (node (ref "U$6") (pin "16") (pinfunction "VCC_16") (pintype "power_in"))
      (node (ref "U$9") (pin "2") (pinfunction "2_2") (pintype "bidirectional"))
    )
    (net (code "70") (name "VEE") (class "Default")
      (node (ref "C_NEG1") (pin "2") (pinfunction "2_2") (pintype "passive"))
      (node (ref "IC1") (pin "-VS") (pinfunction "V-_-VS") (pintype "power_in"))
      (node (ref "IC1") (pin "-VS_B") (pinfunction "V-_-VS_B") (pintype "power_in"))
      (node (ref "IC2") (pin "-VS") (pinfunction "V-_-VS") (pintype "power_in"))
      (node (ref "IC2") (pin "-VS_B") (pinfunction "V-_-VS_B") (pintype "power_in"))
      (node (ref "U$4") (pin "5") (pinfunction "VOUT_5") (pintype "power_in"))
      (node (ref "U$5") (pin "13") (pinfunction "XD_13") (pintype "input"))
      (node (ref "U$5") (pin "4") (pinfunction "XB_4") (pintype "input"))
      (node (ref "U$5") (pin "9") (pinfunction "VEE_9") (pintype "power_in"))
      (node (ref "U$6") (pin "13") (pinfunction "XD_13") (pintype "input"))
      (node (ref "U$6") (pin "4") (pinfunction "XB_4") (pintype "input"))
      (node (ref "U$6") (pin "9") (pinfunction "VEE_9") (pintype "power_in"))
    )
    (net (code "71") (name "unconnected-(U$1-PadP1_4)") (class "Default")
      (node (ref "U$1") (pin "P1_4") (pinfunction "P1_4_P1_4") (pintype "bidirectional"))
    )
    (net (code "72") (name "unconnected-(U$1-PadP1_6)") (class "Default")
      (node (ref "U$1") (pin "P1_6") (pinfunction "P1_6_P1_6") (pintype "bidirectional"))
    )
    (net (code "73") (name "unconnected-(U$1-PadP1_7)") (class "Default")
      (node (ref "U$1") (pin "P1_7") (pinfunction "P1_7_P1_7") (pintype "bidirectional"))
    )
    (net (code "74") (name "unconnected-(U$1-PadP2_0)") (class "Default")
      (node (ref "U$1") (pin "P2_0") (pinfunction "P2_0_P2_0") (pintype "bidirectional"))
    )
    (net (code "75") (name "unconnected-(U$7-Pad2)") (class "Default")
      (node (ref "U$7") (pin "2") (pinfunction "2_2") (pintype "bidirectional"))
    )
    (net (code "76") (name "unconnected-(U$8-4_NC-Pad4)") (class "Default")
      (node (ref "U$8") (pin "4") (pinfunction "4_NC_4") (pintype "no_connect"))
    )
    (net (code "77") (name "unconnected-(U$10-4_NC-Pad4)") (class "Default")
      (node (ref "U$10") (pin "4") (pinfunction "4_NC_4") (pintype "no_connect"))
    )
    (net (code "78") (name "unconnected-(U$17-Pad4)") (class "Default")
      (node (ref "U$17") (pin "4") (pinfunction "4_4") (pintype "bidirectional"))
    )
  )
)
